# HBridge.net
KiCad netlist of a schematic drawn in Altium Designer
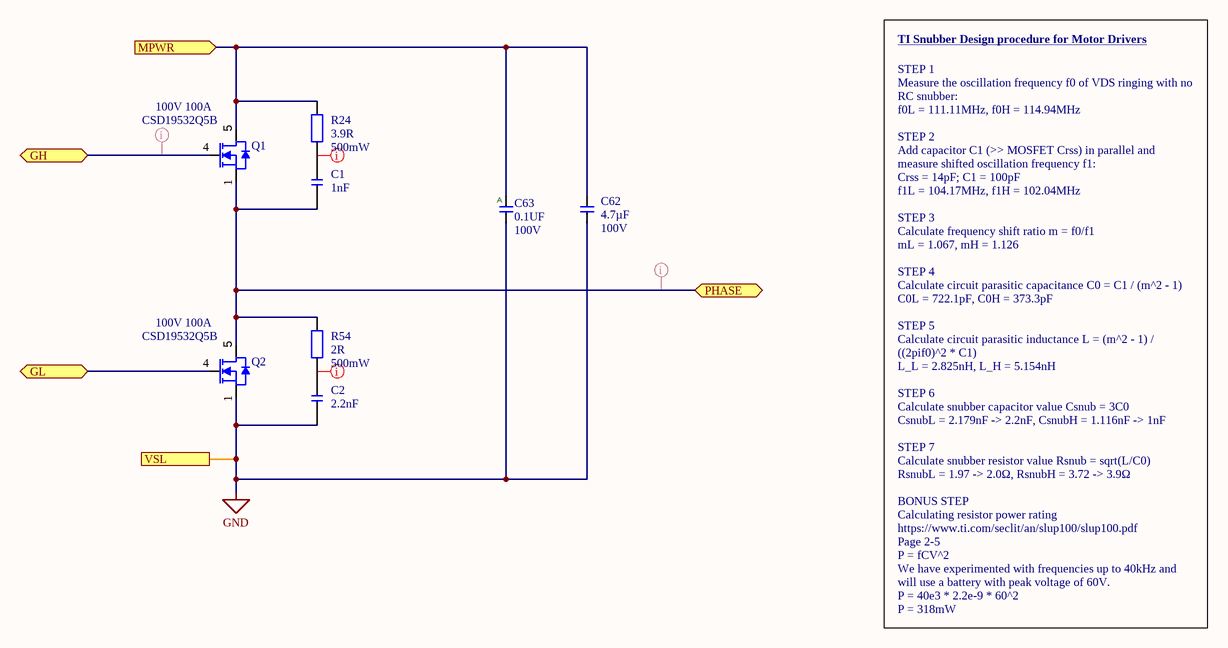
[diagram p0: HBridge.SchDoc]

(export (version "E")
  (design (tool "Eeschema 10.0.6"))
  (components
    (comp (ref "C1")
      (value "1nF")
      (footprint "CAP 0603_1608 RF")
      (description "Automotive grade SMD 0603 capacitor such as Vishay GA....31G series. 1nF 0603 10% X7R 100V")
      (fields (field (name "TOLERANCE") "10%"))
      (libsource (lib "MiscSch1") (part "C"))
    )
    (comp (ref "C2")
      (value "2.2nF")
      (footprint "CAP 0603_1608 RF")
      (description "Automotive grade SMD 0603 capacitor such as Vishay GA....31G series. 2.2nF 0603 10% X7R 100V")
      (fields (field (name "TOLERANCE") "10%"))
      (libsource (lib "MiscSch1") (part "C"))
    )
    (comp (ref "C62")
      (value "CAP_CER_1210_4.7UF_100V_20%_X7S")
      (footprint "C1210")
      (description "CAP CER 4.7UF 100V X7S 1210")
      (fields
        (field (name "MANUFACTURER") "TDK Corporation")
        (field (name "TOLERANCE") "±20%")
        (field (name "VOLTAGE - RATED") "100V")
        (field (name "CAPACITANCE") "4.7µF")
      )
      (libsource (lib "capacitor") (part "CAP_CER_1210_4.7UF_100V_20%_X7S"))
    )
    (comp (ref "C63")
      (value "0.1UF")
      (footprint "C0603")
      (description "CAP, CER, X7S, 0.1uF, 100V, 10%, 0603, AUTOGRADE")
      (fields (field (name "MFG") "TDK") (field (name "VOLTAGE") "100V") (field (name "TOLERANCE") "10%"))
      (libsource (lib "AltiumReleaseLibDB") (part "__Template_Cap_Auto"))
    )
    (comp (ref "NT1")
      (value "Mechanical Feature NET_TIE_10MIL")
      (footprint "NETTIE_10MIL")
      (description "Net Tie, 10mil trace")
      (fields
        (field (name "MANUFACTURER") "Mechanical")
        (field (name "MANUFACTURER PART NUMBER") "NET_TIE_10MIL")
      )
      (libsource (lib "Components") (part "NET_TIE"))
    )
    (comp (ref "Q1")
      (value "100V 100A")
      (footprint "TI_SON5X6")
      (description "MOSFET N-CH 100V 100A 8SON")
      (fields
        (field (name "PART NUMBER") "480-00437-00")
        (field (name "MANUFACTURER") "Texas Instruments")
        (field (name "MANUFACTURER PART NUMBER") "CSD19532Q5B")
      )
      (libsource (lib "Components") (part "NFET_POWER33"))
    )
    (comp (ref "Q2")
      (value "100V 100A")
      (footprint "TI_SON5X6")
      (description "MOSFET N-CH 100V 100A 8SON")
      (fields
        (field (name "PART NUMBER") "480-00437-00")
        (field (name "MANUFACTURER") "Texas Instruments")
        (field (name "MANUFACTURER PART NUMBER") "CSD19532Q5B")
      )
      (libsource (lib "Components") (part "NFET_POWER33"))
    )
    (comp (ref "R24")
      (value "3.9R")
      (footprint "RES 0805_2012 RF")
      (description "High power thick film 0805 resistor such as Vishay CRCW-HP e3 series CRCW08053R90DKEAHP")
      (fields (field (name "TOLERANCE") "1%") (field (name "POWER RATING") "500mW"))
      (libsource (lib "MiscSch1") (part "R"))
    )
    (comp (ref "R54")
      (value "2R")
      (footprint "RES 0805_2012 RF")
      (description "High power thick film 0805 resistor such as Vishay CRCW-HP e3 series CRCW08052R00DKEAHP")
      (fields (field (name "TOLERANCE") "1%") (field (name "POWER RATING") "500mW"))
      (libsource (lib "MiscSch1") (part "R"))
    )
  )
  (nets
    (net (code "1") (name "/GH") (class "Default")
      (node (ref "Q1") (pin "4") (pinfunction "G_4") (pintype "passive"))
    )
    (net (code "2") (name "/GL") (class "Default")
      (node (ref "Q2") (pin "4") (pinfunction "G_4") (pintype "passive"))
    )
    (net (code "3") (name "/MPWR") (class "Default")
      (node (ref "C62") (pin "1") (pintype "passive"))
      (node (ref "C63") (pin "1") (pintype "passive"))
      (node (ref "Q1") (pin "5") (pinfunction "D_5") (pintype "passive"))
      (node (ref "R24") (pin "2") (pinfunction "2_2") (pintype "passive"))
    )
    (net (code "4") (name "/PHASE") (class "Default")
      (node (ref "C1") (pin "1") (pinfunction "1_1") (pintype "passive"))
      (node (ref "Q1") (pin "1") (pinfunction "S_1") (pintype "passive"))
      (node (ref "Q2") (pin "5") (pinfunction "D_5") (pintype "passive"))
      (node (ref "R54") (pin "2") (pinfunction "2_2") (pintype "passive"))
    )
    (net (code "5") (name "/VSL") (class "Default")
      (node (ref "NT1") (pin "1") (pinfunction "1_1") (pintype "passive"))
    )
    (net (code "6") (name "GND") (class "Default")
      (node (ref "C2") (pin "1") (pinfunction "1_1") (pintype "passive"))
      (node (ref "C62") (pin "2") (pintype "passive"))
      (node (ref "C63") (pin "2") (pintype "passive"))
      (node (ref "NT1") (pin "2") (pinfunction "2_2") (pintype "passive"))
      (node (ref "Q2") (pin "1") (pinfunction "S_1") (pintype "passive"))
    )
    (net (code "7") (name "Net-(C1-Pad2)") (class "Default")
      (node (ref "C1") (pin "2") (pinfunction "2_2") (pintype "passive"))
      (node (ref "R24") (pin "1") (pinfunction "1_1") (pintype "passive"))
    )
    (net (code "8") (name "Net-(C2-Pad2)") (class "Default")
      (node (ref "C2") (pin "2") (pinfunction "2_2") (pintype "passive"))
      (node (ref "R54") (pin "1") (pinfunction "1_1") (pintype "passive"))
    )
  )
)
